# CH32F203RBT6-R1.net
KiCad netlist of a schematic drawn in Altium Designer
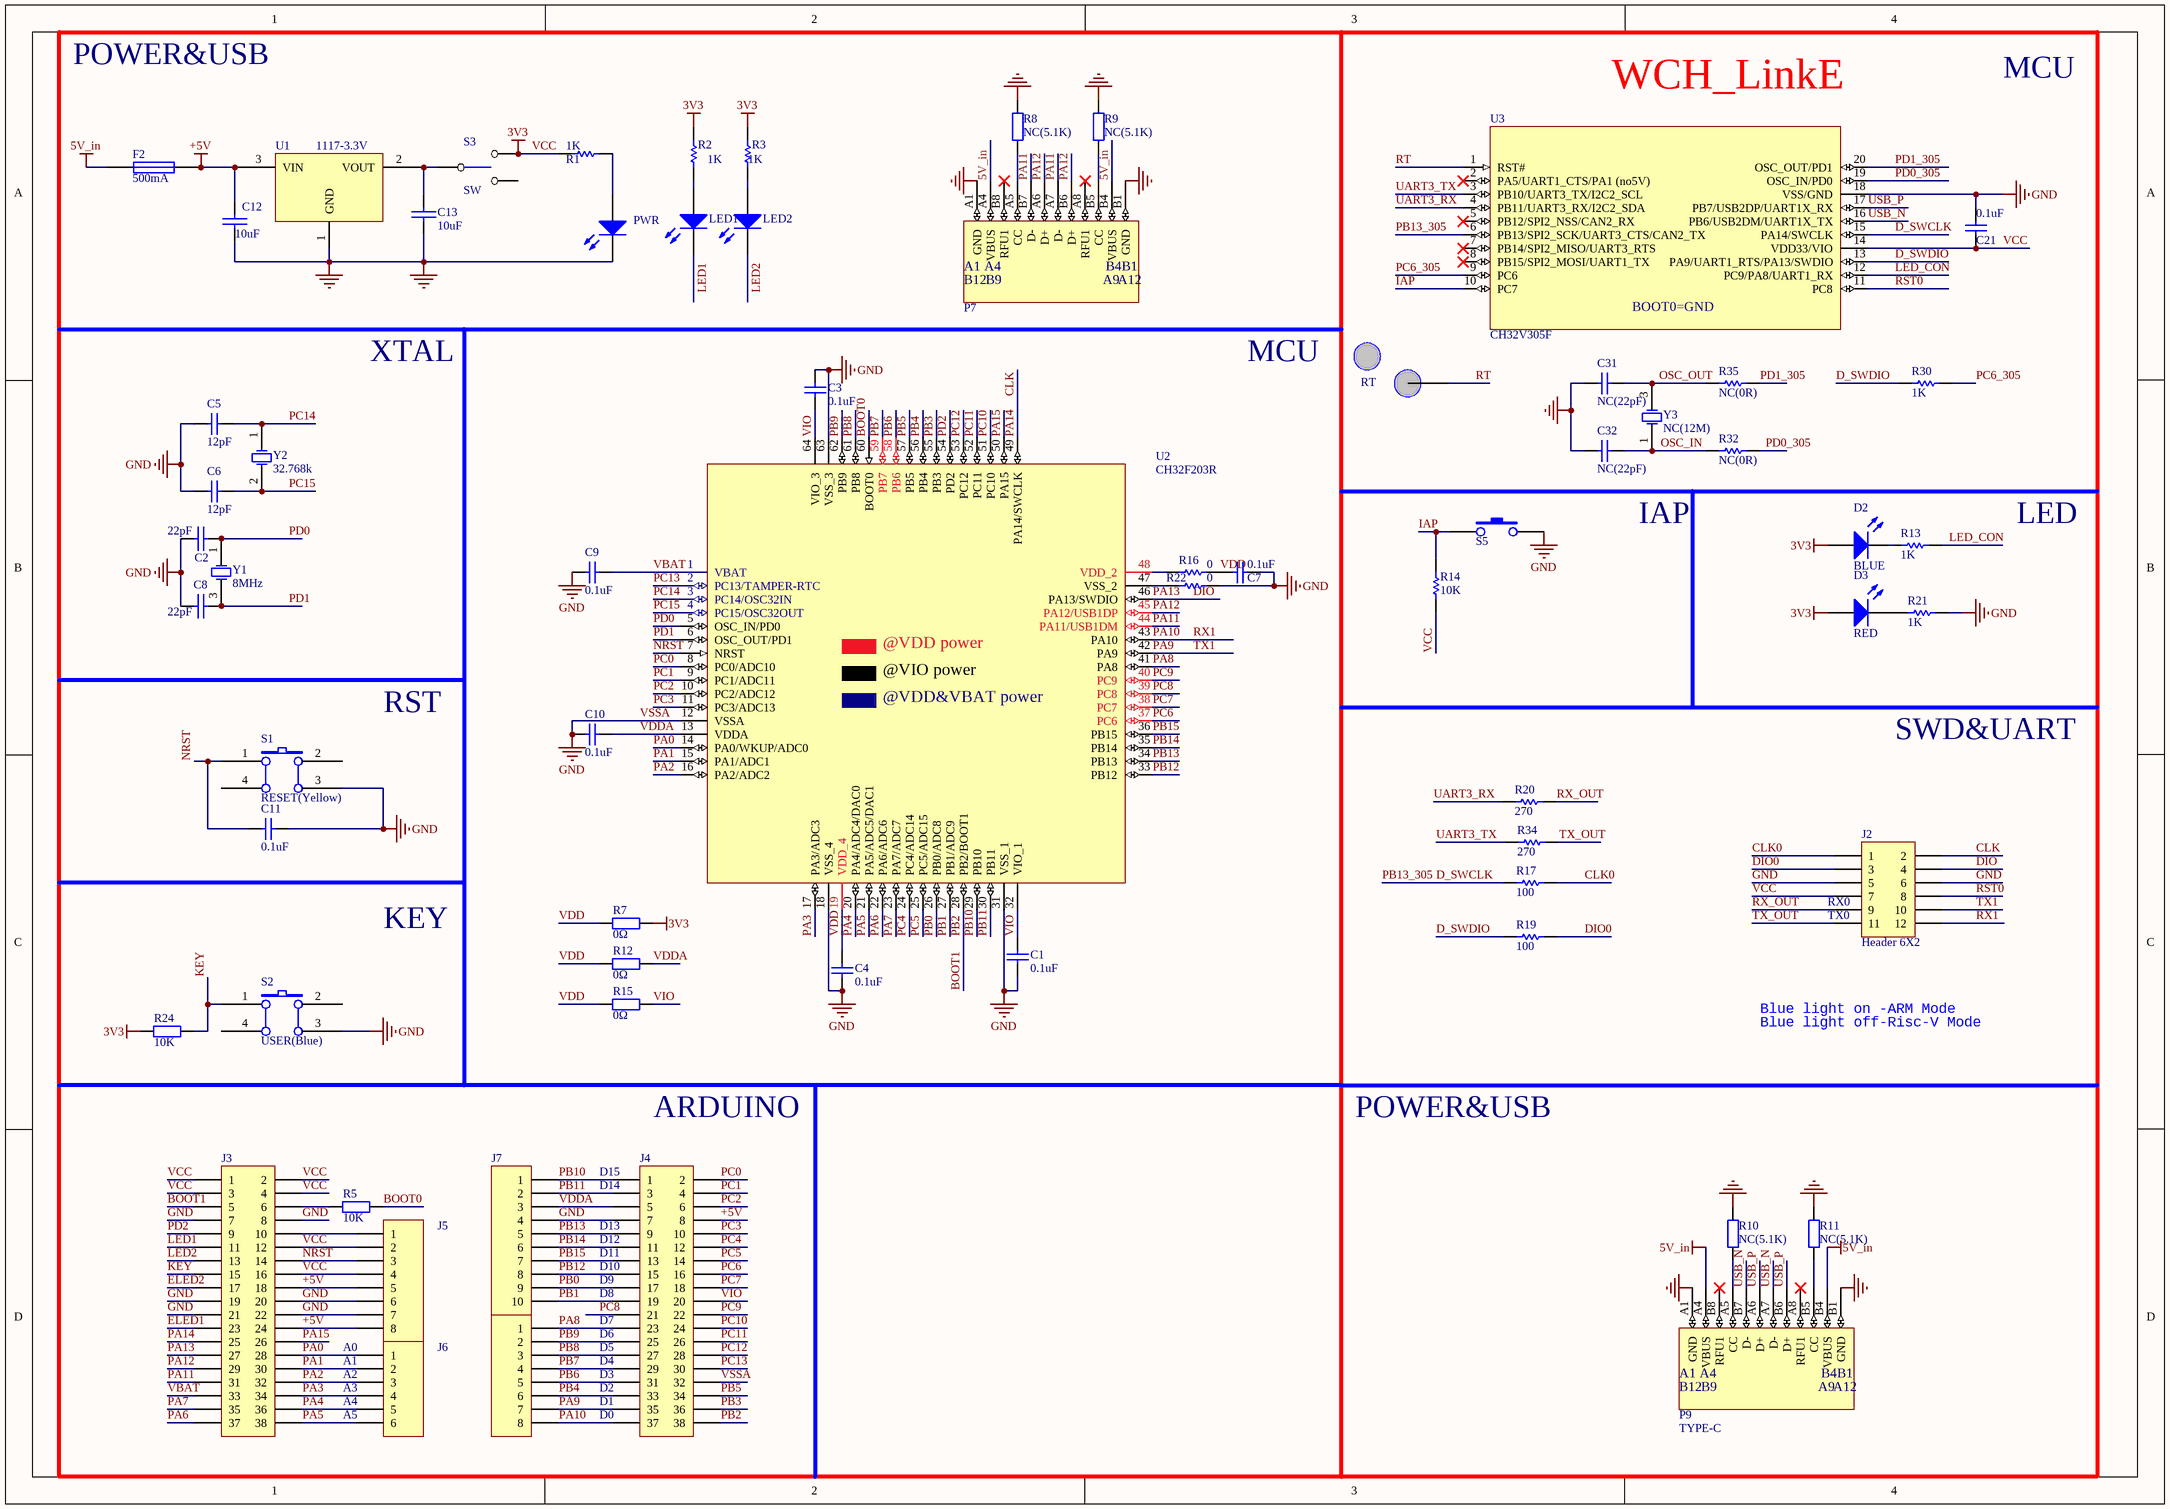
[diagram p0: CH32F203RBT6-R1.SchDoc]

(export (version "E")
  (design (tool "Eeschema 10.0.6"))
  (components
    (comp (ref "C1")
      (value "0.1uF")
      (footprint "0603_C")
      (description "Capacitor")
      (libsource (lib "Miscellaneous Devices") (part "Cap"))
    )
    (comp (ref "C2")
      (value "22pF")
      (footprint "0603_C")
      (description "Capacitor")
      (libsource (lib "*") (part "CAP"))
    )
    (comp (ref "C3")
      (value "0.1uF")
      (footprint "0603_C")
      (description "Capacitor")
      (libsource (lib "Miscellaneous Devices") (part "Cap"))
    )
    (comp (ref "C4")
      (value "0.1uF")
      (footprint "0603_C")
      (description "Capacitor")
      (libsource (lib "Miscellaneous Devices") (part "Cap"))
    )
    (comp (ref "C5")
      (value "12pF")
      (footprint "0603_C")
      (description "Capacitor")
      (libsource (lib "Miscellaneous Devices") (part "Cap"))
    )
    (comp (ref "C6")
      (value "12pF")
      (footprint "0603_C")
      (description "Capacitor")
      (libsource (lib "Miscellaneous Devices") (part "Cap"))
    )
    (comp (ref "C7")
      (value "0.1uF")
      (footprint "0603_C")
      (description "Capacitor")
      (libsource (lib "Miscellaneous Devices") (part "Cap"))
    )
    (comp (ref "C8")
      (value "22pF")
      (footprint "0603_C")
      (description "Capacitor")
      (libsource (lib "*") (part "CAP"))
    )
    (comp (ref "C9")
      (value "0.1uF")
      (footprint "0603_C")
      (description "Capacitor")
      (libsource (lib "Miscellaneous Devices") (part "Cap"))
    )
    (comp (ref "C10")
      (value "0.1uF")
      (footprint "0603_C")
      (description "Capacitor")
      (libsource (lib "Miscellaneous Devices") (part "Cap"))
    )
    (comp (ref "C11")
      (value "0.1uF")
      (footprint "0603_C")
      (description "Capacitor")
      (libsource (lib "Miscellaneous Devices") (part "Cap"))
    )
    (comp (ref "C12")
      (value "10uF")
      (footprint "3216_C")
      (description "Capacitor")
      (libsource (lib "*") (part "CAP"))
    )
    (comp (ref "C13")
      (value "10uF")
      (footprint "3216_C")
      (description "Capacitor")
      (libsource (lib "*") (part "CAP"))
    )
    (comp (ref "C21")
      (value "0.1uF")
      (footprint "0603_C")
      (description "Capacitor")
      (libsource (lib "Miscellaneous Devices") (part "Cap"))
    )
    (comp (ref "C31")
      (value "NC(22pF)")
      (footprint "0603_C")
      (description "Capacitor")
      (fields (field (name "PUBLISHER") "Altium Limited"))
      (libsource (lib "*") (part "Cap"))
    )
    (comp (ref "C32")
      (value "NC(22pF)")
      (footprint "0603_C")
      (description "Capacitor")
      (fields (field (name "PUBLISHER") "Altium Limited"))
      (libsource (lib "*") (part "Cap"))
    )
    (comp (ref "D2")
      (value "BLUE")
      (footprint "0603+")
      (description "Typical RED, GREEN, YELLOW, AMBER GaAs LED")
      (fields (field (name "PUBLISHER") "Altium Limited"))
      (libsource (lib "MYLIB") (part "D0603"))
    )
    (comp (ref "D3")
      (value "RED")
      (footprint "0603+")
      (description "Typical RED, GREEN, YELLOW, AMBER GaAs LED")
      (fields (field (name "PUBLISHER") "Altium Limited"))
      (libsource (lib "MYLIB") (part "D0603"))
    )
    (comp (ref "F2")
      (value "500mA")
      (footprint "0805")
      (description "Fuse")
      (libsource (lib "*") (part "FUSE1"))
    )
    (comp (ref "J2")
      (value "Header 6X2")
      (footprint "IDC12-2.54mm")
      (description "Header, 6-Pin, Dual row")
      (fields (field (name "PUBLISHER") "Altium Limited"))
      (libsource (lib "Miscellaneous Connectors") (part "Header 6X2"))
    )
    (comp (ref "J3")
      (value "Header 19X2")
      (footprint "IDC38-2.54mm")
      (description "Header, 19-Pin, Dual row")
      (fields (field (name "PUBLISHER") "Altium Limited"))
      (libsource (lib "Miscellaneous Connectors") (part "Header 19X2"))
    )
    (comp (ref "J4")
      (value "Header 19X2")
      (footprint "IDC38-2.54mm")
      (description "Header, 19-Pin, Dual row")
      (fields (field (name "PUBLISHER") "Altium Limited"))
      (libsource (lib "Miscellaneous Connectors") (part "Header 19X2"))
    )
    (comp (ref "J5")
      (value "Header 8")
      (footprint "SIP8-2.54mm")
      (description "Header, 8-Pin")
      (fields (field (name "PUBLISHER") "Altium Limited"))
      (libsource (lib "") (part "Header 8_1"))
    )
    (comp (ref "J6")
      (value "Header 6")
      (footprint "SIP6-2.54MM")
      (description "Header, 6-Pin")
      (fields (field (name "PUBLISHER") "Altium Limited"))
      (libsource (lib "Miscellaneous Connectors") (part "Header 6"))
    )
    (comp (ref "J7")
      (value "Header 10")
      (footprint "SIP10-2.54mm")
      (description "Header, 10-Pin")
      (fields (field (name "PUBLISHER") "Altium Limited"))
      (libsource (lib "Miscellaneous Connectors") (part "Header 10"))
    )
    (comp (ref "J8")
      (value "Header 8")
      (footprint "SIP8-2.54mm")
      (description "Header, 8-Pin")
      (fields (field (name "PUBLISHER") "Altium Limited"))
      (libsource (lib "Miscellaneous Connectors") (part "Header 8"))
    )
    (comp (ref "LED1")
      (value "LED1   blue")
      (footprint "0603+")
      (description "Typical INFRARED GaAs LED")
      (fields (field (name "PUBLISHER") "Altium Limited"))
      (libsource (lib "Miscellaneous Devices") (part "LED0"))
    )
    (comp (ref "LED2")
      (value "LED2  blue")
      (footprint "0603+")
      (description "Typical INFRARED GaAs LED")
      (fields (field (name "PUBLISHER") "Altium Limited"))
      (libsource (lib "Miscellaneous Devices") (part "LED0"))
    )
    (comp (ref "P7")
      (value "TYPE-C")
      (footprint "TYPE-C-Receptacle-2.0")
      (libsource (lib "*") (part "TYPE-C1"))
    )
    (comp (ref "P9")
      (value "TYPE-C")
      (footprint "TYPE-C-Receptacle-2.0")
      (libsource (lib "*") (part "TYPE-C1"))
    )
    (comp (ref "PWR")
      (value "POWER  red")
      (footprint "0603+")
      (description "Typical INFRARED GaAs LED")
      (fields (field (name "PUBLISHER") "Altium Limited"))
      (libsource (lib "Miscellaneous Devices") (part "LED0"))
    )
    (comp (ref "R1")
      (value "1K")
      (footprint "0603")
      (description "Semiconductor Resistor")
      (libsource (lib "Miscellaneous Devices") (part "Res Semi"))
    )
    (comp (ref "R2")
      (value "1K")
      (footprint "0603")
      (description "Semiconductor Resistor")
      (libsource (lib "Miscellaneous Devices") (part "Res Semi"))
    )
    (comp (ref "R3")
      (value "1K")
      (footprint "0603")
      (description "Semiconductor Resistor")
      (libsource (lib "Miscellaneous Devices") (part "Res Semi"))
    )
    (comp (ref "R5")
      (value "10K")
      (footprint "0603")
      (description "Resistor")
      (libsource (lib "") (part "Res2_2"))
    )
    (comp (ref "R7")
      (value "0Ω")
      (footprint "0603")
      (description "Resistor")
      (libsource (lib "Miscellaneous Devices") (part "Res2"))
    )
    (comp (ref "R8")
      (value "NC(5.1K)")
      (footprint "0603")
      (description "Resistor")
      (libsource (lib "") (part "Res2_1"))
    )
    (comp (ref "R9")
      (value "NC(5.1K)")
      (footprint "0603")
      (description "Resistor")
      (libsource (lib "") (part "Res2_1"))
    )
    (comp (ref "R10")
      (value "NC(5.1K)")
      (footprint "0603")
      (description "Resistor")
      (libsource (lib "") (part "Res2_3"))
    )
    (comp (ref "R11")
      (value "NC(5.1K)")
      (footprint "0603")
      (description "Resistor")
      (libsource (lib "") (part "Res2_3"))
    )
    (comp (ref "R12")
      (value "0Ω")
      (footprint "0603")
      (description "Resistor")
      (libsource (lib "Miscellaneous Devices") (part "Res2"))
    )
    (comp (ref "R13")
      (value "1K")
      (footprint "0603")
      (description "Resistor")
      (fields (field (name "PUBLISHER") "Altium Limited"))
      (libsource (lib "MYLIB") (part "0603-1"))
    )
    (comp (ref "R14")
      (value "10K")
      (footprint "0603")
      (description "Resistor")
      (fields (field (name "PUBLISHER") "Altium Limited"))
      (libsource (lib "MYLIB") (part "0603-1"))
    )
    (comp (ref "R15")
      (value "0Ω")
      (footprint "0603")
      (description "Resistor")
      (libsource (lib "Miscellaneous Devices") (part "Res2"))
    )
    (comp (ref "R16")
      (value "0")
      (footprint "0603")
      (description "Resistor")
      (fields (field (name "PUBLISHER") "Altium Limited"))
      (libsource (lib "MYLIB") (part "0603-1"))
    )
    (comp (ref "R17")
      (value "100")
      (footprint "0603")
      (description "Resistor")
      (fields (field (name "PUBLISHER") "Altium Limited"))
      (libsource (lib "MYLIB") (part "0603-1"))
    )
    (comp (ref "R19")
      (value "100")
      (footprint "0603")
      (description "Resistor")
      (fields (field (name "PUBLISHER") "Altium Limited"))
      (libsource (lib "MYLIB") (part "0603-1"))
    )
    (comp (ref "R20")
      (value "270")
      (footprint "0603")
      (description "Resistor")
      (fields (field (name "PUBLISHER") "Altium Limited"))
      (libsource (lib "MYLIB") (part "0603-1"))
    )
    (comp (ref "R21")
      (value "1K")
      (footprint "0603")
      (description "Resistor")
      (fields (field (name "PUBLISHER") "Altium Limited"))
      (libsource (lib "MYLIB") (part "0603-1"))
    )
    (comp (ref "R22")
      (value "0")
      (footprint "0603")
      (description "Resistor")
      (fields (field (name "PUBLISHER") "Altium Limited"))
      (libsource (lib "MYLIB") (part "0603-1"))
    )
    (comp (ref "R24")
      (value "10K")
      (footprint "0603")
      (description "Resistor")
      (libsource (lib "Miscellaneous Devices") (part "Res2"))
    )
    (comp (ref "R30")
      (value "1K")
      (footprint "0603")
      (description "Resistor")
      (fields (field (name "PUBLISHER") "Altium Limited"))
      (libsource (lib "MYLIB") (part "0603-1"))
    )
    (comp (ref "R32")
      (value "NC(0R)")
      (footprint "0603")
      (description "Resistor")
      (fields (field (name "PUBLISHER") "Altium Limited"))
      (libsource (lib "MYLIB") (part "0603-1"))
    )
    (comp (ref "R34")
      (value "270")
      (footprint "0603")
      (description "Resistor")
      (fields (field (name "PUBLISHER") "Altium Limited"))
      (libsource (lib "MYLIB") (part "0603-1"))
    )
    (comp (ref "R35")
      (value "NC(0R)")
      (footprint "0603")
      (description "Resistor")
      (fields (field (name "PUBLISHER") "Altium Limited"))
      (libsource (lib "MYLIB") (part "0603-1"))
    )
    (comp (ref "RT")
      (value "Testpoint")
      (footprint "TESTPOINT1")
      (description "测试点")
      (libsource (lib "wch_sch_others") (part "Testpoint"))
    )
    (comp (ref "S1")
      (value "RESET(Yellow)")
      (footprint "KEYX")
      (description "SE PUSHBUTTON")
      (libsource (lib "Documents") (part "SW PUSHBUTTON"))
    )
    (comp (ref "S2")
      (value "USER(Blue)")
      (footprint "KEYX")
      (description "SE PUSHBUTTON")
      (libsource (lib "Documents") (part "SW PUSHBUTTON"))
    )
    (comp (ref "S3") (value "SW") (footprint "SW1") (libsource (lib "MYSCH") (part "SW")))
    (comp (ref "S5") (value "KEY") (footprint "贴片按键") (libsource (lib "*") (part "KEY")))
    (comp (ref "U1")
      (value "1117-3.3V")
      (footprint "SOT-223")
      (libsource (lib "wch_sch_others") (part "1117-3.3V"))
    )
    (comp (ref "U2")
      (value "CH32F203R")
      (footprint "LQFP64M_10x10")
      (description "ARM M3 HD-MCU, 144MHz, 8*UART, 10*Timer, 4*OPA")
      (libsource (lib "CHXXX") (part "CH32F203R"))
    )
    (comp (ref "U3")
      (value "CH32V305F")
      (footprint "TSSOP20")
      (description "RISC-V FPU HD-MCU, 144MHz, USB_480M, CAN, UART*2, SPI")
      (libsource (lib "CHXXX") (part "CH32V305F"))
    )
    (comp (ref "Y1")
      (value "8MHz")
      (footprint "XT3225")
      (description "Crystal Oscillator")
      (fields (field (name "PUBLISHER") "Altium Limited"))
      (libsource (lib "*") (part "XTAL"))
    )
    (comp (ref "Y2")
      (value "32.768k")
      (footprint "FC-135")
      (description "Crystal Oscillator")
      (fields (field (name "PUBLISHER") "Altium Limited"))
      (libsource (lib "Miscellaneous Devices") (part "XTAL"))
    )
    (comp (ref "Y3")
      (value "NC(12M)")
      (footprint "XT3225")
      (description "Crystal Oscillator")
      (libsource (lib "*") (part "XTAL"))
    )
  )
  (nets
    (net (code "1") (name "+5V") (class "Default")
      (node (ref "C12") (pin "1") (pinfunction "1_1") (pintype "passive"))
      (node (ref "F2") (pin "2") (pinfunction "2_2") (pintype "passive"))
      (node (ref "J3") (pin "18") (pinfunction "18_18") (pintype "passive"))
      (node (ref "J3") (pin "24") (pinfunction "24_24") (pintype "passive"))
      (node (ref "J4") (pin "8") (pinfunction "8_8") (pintype "passive"))
      (node (ref "J5") (pin "5") (pinfunction "5_5") (pintype "passive"))
      (node (ref "J5") (pin "8") (pinfunction "8_8") (pintype "passive"))
      (node (ref "U1") (pin "3") (pinfunction "VIN_3") (pintype "passive"))
    )
    (net (code "2") (name "/BOOT0") (class "Default")
      (node (ref "R5") (pin "2") (pinfunction "2_2") (pintype "passive"))
      (node (ref "U2") (pin "60") (pinfunction "BOOT0_60") (pintype "input"))
    )
    (net (code "3") (name "/BOOT1") (class "Default")
      (node (ref "J3") (pin "5") (pinfunction "5_5") (pintype "passive"))
      (node (ref "J4") (pin "38") (pinfunction "38_38") (pintype "passive"))
      (node (ref "U2") (pin "28") (pinfunction "PB2/BOOT1_28") (pintype "bidirectional"))
    )
    (net (code "4") (name "/CLK") (class "Default")
      (node (ref "J2") (pin "2") (pinfunction "2_2") (pintype "passive"))
      (node (ref "J3") (pin "25") (pinfunction "25_25") (pintype "passive"))
      (node (ref "U2") (pin "49") (pinfunction "PA14/SWCLK_49") (pintype "bidirectional"))
    )
    (net (code "5") (name "/CLK0") (class "Default")
      (node (ref "J2") (pin "1") (pinfunction "1_1") (pintype "passive"))
      (node (ref "R17") (pin "1") (pinfunction "1_1") (pintype "passive"))
    )
    (net (code "6") (name "/DIO") (class "Default")
      (node (ref "J2") (pin "4") (pinfunction "4_4") (pintype "passive"))
      (node (ref "J3") (pin "27") (pinfunction "27_27") (pintype "passive"))
      (node (ref "U2") (pin "46") (pinfunction "PA13/SWDIO_46") (pintype "bidirectional"))
    )
    (net (code "7") (name "/DIO0") (class "Default")
      (node (ref "J2") (pin "3") (pinfunction "3_3") (pintype "passive"))
      (node (ref "R19") (pin "1") (pinfunction "1_1") (pintype "passive"))
    )
    (net (code "8") (name "/D_SWCLK") (class "Default")
      (node (ref "R17") (pin "2") (pinfunction "2_2") (pintype "passive"))
      (node (ref "U3") (pin "15") (pinfunction "PA14/SWCLK_15") (pintype "bidirectional"))
      (node (ref "U3") (pin "6") (pinfunction "PB13/SPI2_SCK/UART3_CTS/CAN2_TX_6") (pintype "bidirectional"))
    )
    (net (code "9") (name "/D_SWDIO") (class "Default")
      (node (ref "R19") (pin "2") (pinfunction "2_2") (pintype "passive"))
      (node (ref "R30") (pin "1") (pinfunction "1_1") (pintype "passive"))
      (node (ref "U3") (pin "13") (pinfunction "PA9/UART1_RTS/PA13/SWDIO_13") (pintype "bidirectional"))
    )
    (net (code "10") (name "/ELED1") (class "Default")
      (node (ref "J3") (pin "23") (pinfunction "23_23") (pintype "passive"))
    )
    (net (code "11") (name "/ELED2") (class "Default")
      (node (ref "J3") (pin "17") (pinfunction "17_17") (pintype "passive"))
    )
    (net (code "12") (name "/IAP") (class "Default")
      (node (ref "R14") (pin "1") (pinfunction "1_1") (pintype "passive"))
      (node (ref "S5") (pin "1") (pinfunction "1_1") (pintype "passive"))
      (node (ref "U3") (pin "10") (pinfunction "PC7_10") (pintype "bidirectional"))
    )
    (net (code "13") (name "/KEY") (class "Default")
      (node (ref "J3") (pin "15") (pinfunction "15_15") (pintype "passive"))
      (node (ref "R24") (pin "1") (pinfunction "1_1") (pintype "passive"))
      (node (ref "S2") (pin "1") (pinfunction "A0_1") (pintype "passive"))
    )
    (net (code "14") (name "/LED1") (class "Default")
      (node (ref "J3") (pin "11") (pinfunction "11_11") (pintype "passive"))
      (node (ref "LED1") (pin "2") (pinfunction "K_2") (pintype "passive"))
    )
    (net (code "15") (name "/LED2") (class "Default")
      (node (ref "J3") (pin "13") (pinfunction "13_13") (pintype "passive"))
      (node (ref "LED2") (pin "2") (pinfunction "K_2") (pintype "passive"))
    )
    (net (code "16") (name "/LED_CON") (class "Default")
      (node (ref "R13") (pin "1") (pinfunction "1_1") (pintype "passive"))
      (node (ref "U3") (pin "12") (pinfunction "PC9/PA8/UART1_RX_12") (pintype "bidirectional"))
    )
    (net (code "17") (name "/NRST") (class "Default")
      (node (ref "C11") (pin "2") (pinfunction "2_2") (pintype "passive"))
      (node (ref "J3") (pin "14") (pinfunction "14_14") (pintype "passive"))
      (node (ref "J5") (pin "3") (pinfunction "3_3") (pintype "passive"))
      (node (ref "S1") (pin "1") (pinfunction "A0_1") (pintype "passive"))
      (node (ref "U2") (pin "7") (pinfunction "NRST_7") (pintype "input"))
    )
    (net (code "18") (name "/OSC_IN") (class "Default")
      (node (ref "C32") (pin "2") (pinfunction "2_2") (pintype "passive"))
      (node (ref "R32") (pin "2") (pinfunction "2_2") (pintype "passive"))
      (node (ref "Y3") (pin "1") (pinfunction "OSC1_1") (pintype "passive"))
    )
    (net (code "19") (name "/OSC_OUT") (class "Default")
      (node (ref "C31") (pin "2") (pinfunction "2_2") (pintype "passive"))
      (node (ref "R35") (pin "2") (pinfunction "2_2") (pintype "passive"))
      (node (ref "Y3") (pin "3") (pinfunction "OSC2_3") (pintype "passive"))
    )
    (net (code "20") (name "/PA0") (class "Default")
      (node (ref "J3") (pin "28") (pinfunction "28_28") (pintype "passive"))
      (node (ref "J6") (pin "1") (pinfunction "1_1") (pintype "passive"))
      (node (ref "U2") (pin "14") (pinfunction "PA0/WKUP/ADC0_14") (pintype "bidirectional"))
    )
    (net (code "21") (name "/PA1") (class "Default")
      (node (ref "J3") (pin "30") (pinfunction "30_30") (pintype "passive"))
      (node (ref "J6") (pin "2") (pinfunction "2_2") (pintype "passive"))
      (node (ref "U2") (pin "15") (pinfunction "PA1/ADC1_15") (pintype "bidirectional"))
    )
    (net (code "22") (name "/PA2") (class "Default")
      (node (ref "J3") (pin "32") (pinfunction "32_32") (pintype "passive"))
      (node (ref "J6") (pin "3") (pinfunction "3_3") (pintype "passive"))
      (node (ref "U2") (pin "16") (pinfunction "PA2/ADC2_16") (pintype "bidirectional"))
    )
    (net (code "23") (name "/PA3") (class "Default")
      (node (ref "J3") (pin "34") (pinfunction "34_34") (pintype "passive"))
      (node (ref "J6") (pin "4") (pinfunction "4_4") (pintype "passive"))
      (node (ref "U2") (pin "17") (pinfunction "PA3/ADC3_17") (pintype "bidirectional"))
    )
    (net (code "24") (name "/PA4") (class "Default")
      (node (ref "J3") (pin "36") (pinfunction "36_36") (pintype "passive"))
      (node (ref "J6") (pin "5") (pinfunction "5_5") (pintype "passive"))
      (node (ref "U2") (pin "20") (pinfunction "PA4/ADC4/DAC0_20") (pintype "bidirectional"))
    )
    (net (code "25") (name "/PA5") (class "Default")
      (node (ref "J3") (pin "38") (pinfunction "38_38") (pintype "passive"))
      (node (ref "J6") (pin "6") (pinfunction "6_6") (pintype "passive"))
      (node (ref "U2") (pin "21") (pinfunction "PA5/ADC5/DAC1_21") (pintype "bidirectional"))
    )
    (net (code "26") (name "/PA6") (class "Default")
      (node (ref "J3") (pin "37") (pinfunction "37_37") (pintype "passive"))
      (node (ref "U2") (pin "22") (pinfunction "PA6/ADC6_22") (pintype "bidirectional"))
    )
    (net (code "27") (name "/PA7") (class "Default")
      (node (ref "J3") (pin "35") (pinfunction "35_35") (pintype "passive"))
      (node (ref "U2") (pin "23") (pinfunction "PA7/ADC7_23") (pintype "bidirectional"))
    )
    (net (code "28") (name "/PA8") (class "Default")
      (node (ref "J4") (pin "23") (pinfunction "23_23") (pintype "passive"))
      (node (ref "J8") (pin "1") (pinfunction "1_1") (pintype "passive"))
      (node (ref "U2") (pin "41") (pinfunction "PA8_41") (pintype "bidirectional"))
    )
    (net (code "29") (name "/PA9") (class "Default")
      (node (ref "J2") (pin "10") (pinfunction "10_10") (pintype "passive"))
      (node (ref "J4") (pin "35") (pinfunction "35_35") (pintype "passive"))
      (node (ref "J8") (pin "7") (pinfunction "7_7") (pintype "passive"))
      (node (ref "U2") (pin "42") (pinfunction "PA9_42") (pintype "bidirectional"))
    )
    (net (code "30") (name "/PA10") (class "Default")
      (node (ref "J2") (pin "12") (pinfunction "12_12") (pintype "passive"))
      (node (ref "J4") (pin "37") (pinfunction "37_37") (pintype "passive"))
      (node (ref "J8") (pin "8") (pinfunction "8_8") (pintype "passive"))
      (node (ref "U2") (pin "43") (pinfunction "PA10_43") (pintype "bidirectional"))
    )
    (net (code "31") (name "/PA11") (class "Default")
      (node (ref "J3") (pin "31") (pinfunction "31_31") (pintype "passive"))
      (node (ref "P7") (pin "A7") (pinfunction "D-_A7") (pintype "bidirectional"))
      (node (ref "P7") (pin "B7") (pinfunction "D-_B7") (pintype "bidirectional"))
      (node (ref "U2") (pin "44") (pinfunction "PA11/USB1DM_44") (pintype "bidirectional"))
    )
    (net (code "32") (name "/PA12") (class "Default")
      (node (ref "J3") (pin "29") (pinfunction "29_29") (pintype "passive"))
      (node (ref "P7") (pin "A6") (pinfunction "D+_A6") (pintype "bidirectional"))
      (node (ref "P7") (pin "B6") (pinfunction "D+_B6") (pintype "bidirectional"))
      (node (ref "U2") (pin "45") (pinfunction "PA12/USB1DP_45") (pintype "bidirectional"))
    )
    (net (code "33") (name "/PA15") (class "Default")
      (node (ref "J3") (pin "26") (pinfunction "26_26") (pintype "passive"))
      (node (ref "U2") (pin "50") (pinfunction "PA15_50") (pintype "bidirectional"))
    )
    (net (code "34") (name "/PB0") (class "Default")
      (node (ref "J4") (pin "17") (pinfunction "17_17") (pintype "passive"))
      (node (ref "J7") (pin "9") (pinfunction "9_9") (pintype "passive"))
      (node (ref "U2") (pin "26") (pinfunction "PB0/ADC8_26") (pintype "bidirectional"))
    )
    (net (code "35") (name "/PB1") (class "Default")
      (node (ref "J4") (pin "19") (pinfunction "19_19") (pintype "passive"))
      (node (ref "J7") (pin "10") (pinfunction "10_10") (pintype "passive"))
      (node (ref "U2") (pin "27") (pinfunction "PB1/ADC9_27") (pintype "bidirectional"))
    )
    (net (code "36") (name "/PB3") (class "Default")
      (node (ref "J4") (pin "36") (pinfunction "36_36") (pintype "passive"))
      (node (ref "U2") (pin "55") (pinfunction "PB3_55") (pintype "bidirectional"))
    )
    (net (code "37") (name "/PB4") (class "Default")
      (node (ref "J4") (pin "33") (pinfunction "33_33") (pintype "passive"))
      (node (ref "J8") (pin "6") (pinfunction "6_6") (pintype "passive"))
      (node (ref "U2") (pin "56") (pinfunction "PB4_56") (pintype "bidirectional"))
    )
    (net (code "38") (name "/PB5") (class "Default")
      (node (ref "J4") (pin "34") (pinfunction "34_34") (pintype "passive"))
      (node (ref "U2") (pin "57") (pinfunction "PB5_57") (pintype "bidirectional"))
    )
    (net (code "39") (name "/PB6") (class "Default")
      (node (ref "J4") (pin "31") (pinfunction "31_31") (pintype "passive"))
      (node (ref "J8") (pin "5") (pinfunction "5_5") (pintype "passive"))
      (node (ref "U2") (pin "58") (pinfunction "PB6_58") (pintype "bidirectional"))
    )
    (net (code "40") (name "/PB7") (class "Default")
      (node (ref "J4") (pin "29") (pinfunction "29_29") (pintype "passive"))
      (node (ref "J8") (pin "4") (pinfunction "4_4") (pintype "passive"))
      (node (ref "U2") (pin "59") (pinfunction "PB7_59") (pintype "bidirectional"))
    )
    (net (code "41") (name "/PB8") (class "Default")
      (node (ref "J4") (pin "27") (pinfunction "27_27") (pintype "passive"))
      (node (ref "J8") (pin "3") (pinfunction "3_3") (pintype "passive"))
      (node (ref "U2") (pin "61") (pinfunction "PB8_61") (pintype "bidirectional"))
    )
    (net (code "42") (name "/PB9") (class "Default")
      (node (ref "J4") (pin "25") (pinfunction "25_25") (pintype "passive"))
      (node (ref "J8") (pin "2") (pinfunction "2_2") (pintype "passive"))
      (node (ref "U2") (pin "62") (pinfunction "PB9_62") (pintype "bidirectional"))
    )
    (net (code "43") (name "/PB10") (class "Default")
      (node (ref "J4") (pin "1") (pinfunction "1_1") (pintype "passive"))
      (node (ref "J7") (pin "1") (pinfunction "1_1") (pintype "passive"))
      (node (ref "U2") (pin "29") (pinfunction "PB10_29") (pintype "bidirectional"))
    )
    (net (code "44") (name "/PB11") (class "Default")
      (node (ref "J4") (pin "3") (pinfunction "3_3") (pintype "passive"))
      (node (ref "J7") (pin "2") (pinfunction "2_2") (pintype "passive"))
      (node (ref "U2") (pin "30") (pinfunction "PB11_30") (pintype "bidirectional"))
    )
    (net (code "45") (name "/PB12") (class "Default")
      (node (ref "J4") (pin "15") (pinfunction "15_15") (pintype "passive"))
      (node (ref "J7") (pin "8") (pinfunction "8_8") (pintype "passive"))
      (node (ref "U2") (pin "33") (pinfunction "PB12_33") (pintype "bidirectional"))
    )
    (net (code "46") (name "/PB13") (class "Default")
      (node (ref "J4") (pin "9") (pinfunction "9_9") (pintype "passive"))
      (node (ref "J7") (pin "5") (pinfunction "5_5") (pintype "passive"))
      (node (ref "U2") (pin "34") (pinfunction "PB13_34") (pintype "bidirectional"))
    )
    (net (code "47") (name "/PB14") (class "Default")
      (node (ref "J4") (pin "11") (pinfunction "11_11") (pintype "passive"))
      (node (ref "J7") (pin "6") (pinfunction "6_6") (pintype "passive"))
      (node (ref "U2") (pin "35") (pinfunction "PB14_35") (pintype "bidirectional"))
    )
    (net (code "48") (name "/PB15") (class "Default")
      (node (ref "J4") (pin "13") (pinfunction "13_13") (pintype "passive"))
      (node (ref "J7") (pin "7") (pinfunction "7_7") (pintype "passive"))
      (node (ref "U2") (pin "36") (pinfunction "PB15_36") (pintype "bidirectional"))
    )
    (net (code "49") (name "/PC0") (class "Default")
      (node (ref "J4") (pin "2") (pinfunction "2_2") (pintype "passive"))
      (node (ref "U2") (pin "8") (pinfunction "PC0/ADC10_8") (pintype "bidirectional"))
    )
    (net (code "50") (name "/PC1") (class "Default")
      (node (ref "J4") (pin "4") (pinfunction "4_4") (pintype "passive"))
      (node (ref "U2") (pin "9") (pinfunction "PC1/ADC11_9") (pintype "bidirectional"))
    )
    (net (code "51") (name "/PC2") (class "Default")
      (node (ref "J4") (pin "6") (pinfunction "6_6") (pintype "passive"))
      (node (ref "U2") (pin "10") (pinfunction "PC2/ADC12_10") (pintype "bidirectional"))
    )
    (net (code "52") (name "/PC3") (class "Default")
      (node (ref "J4") (pin "10") (pinfunction "10_10") (pintype "passive"))
      (node (ref "U2") (pin "11") (pinfunction "PC3/ADC13_11") (pintype "bidirectional"))
    )
    (net (code "53") (name "/PC4") (class "Default")
      (node (ref "J4") (pin "12") (pinfunction "12_12") (pintype "passive"))
      (node (ref "U2") (pin "24") (pinfunction "PC4/ADC14_24") (pintype "bidirectional"))
    )
    (net (code "54") (name "/PC5") (class "Default")
      (node (ref "J4") (pin "14") (pinfunction "14_14") (pintype "passive"))
      (node (ref "U2") (pin "25") (pinfunction "PC5/ADC15_25") (pintype "bidirectional"))
    )
    (net (code "55") (name "/PC6") (class "Default")
      (node (ref "J4") (pin "16") (pinfunction "16_16") (pintype "passive"))
      (node (ref "U2") (pin "37") (pinfunction "PC6_37") (pintype "bidirectional"))
    )
    (net (code "56") (name "/PC6_305") (class "Default")
      (node (ref "R30") (pin "2") (pinfunction "2_2") (pintype "passive"))
      (node (ref "U3") (pin "9") (pinfunction "PC6_9") (pintype "bidirectional"))
    )
    (net (code "57") (name "/PC7") (class "Default")
      (node (ref "J4") (pin "18") (pinfunction "18_18") (pintype "passive"))
      (node (ref "U2") (pin "38") (pinfunction "PC7_38") (pintype "bidirectional"))
    )
    (net (code "58") (name "/PC8") (class "Default")
      (node (ref "J4") (pin "21") (pinfunction "21_21") (pintype "passive"))
      (node (ref "U2") (pin "39") (pinfunction "PC8_39") (pintype "bidirectional"))
    )
    (net (code "59") (name "/PC9") (class "Default")
      (node (ref "J4") (pin "22") (pinfunction "22_22") (pintype "passive"))
      (node (ref "U2") (pin "40") (pinfunction "PC9_40") (pintype "bidirectional"))
    )
    (net (code "60") (name "/PC10") (class "Default")
      (node (ref "J4") (pin "24") (pinfunction "24_24") (pintype "passive"))
      (node (ref "U2") (pin "51") (pinfunction "PC10_51") (pintype "bidirectional"))
    )
    (net (code "61") (name "/PC11") (class "Default")
      (node (ref "J4") (pin "26") (pinfunction "26_26") (pintype "passive"))
      (node (ref "U2") (pin "52") (pinfunction "PC11_52") (pintype "bidirectional"))
    )
    (net (code "62") (name "/PC12") (class "Default")
      (node (ref "J4") (pin "28") (pinfunction "28_28") (pintype "passive"))
      (node (ref "U2") (pin "53") (pinfunction "PC12_53") (pintype "bidirectional"))
    )
    (net (code "63") (name "/PC13") (class "Default")
      (node (ref "J4") (pin "30") (pinfunction "30_30") (pintype "passive"))
      (node (ref "U2") (pin "2") (pinfunction "PC13/TAMPER-RTC_2") (pintype "bidirectional"))
    )
    (net (code "64") (name "/PC14") (class "Default")
      (node (ref "C5") (pin "1") (pinfunction "1_1") (pintype "passive"))
      (node (ref "U2") (pin "3") (pinfunction "PC14/OSC32IN_3") (pintype "bidirectional"))
      (node (ref "Y2") (pin "1") (pinfunction "OSC1_1") (pintype "passive"))
    )
    (net (code "65") (name "/PC15") (class "Default")
      (node (ref "C6") (pin "1") (pinfunction "1_1") (pintype "passive"))
      (node (ref "U2") (pin "4") (pinfunction "PC15/OSC32OUT_4") (pintype "bidirectional"))
      (node (ref "Y2") (pin "2") (pinfunction "OSC2_2") (pintype "passive"))
    )
    (net (code "66") (name "/PD0") (class "Default")
      (node (ref "C2") (pin "2") (pinfunction "2_2") (pintype "passive"))
      (node (ref "U2") (pin "5") (pinfunction "OSC_IN/PD0_5") (pintype "bidirectional"))
      (node (ref "Y1") (pin "1") (pinfunction "OSC1_1") (pintype "passive"))
    )
    (net (code "67") (name "/PD0_305") (class "Default")
      (node (ref "R32") (pin "1") (pinfunction "1_1") (pintype "passive"))
      (node (ref "U3") (pin "19") (pinfunction "OSC_IN/PD0_19") (pintype "bidirectional"))
    )
    (net (code "68") (name "/PD1") (class "Default")
      (node (ref "C8") (pin "2") (pinfunction "2_2") (pintype "passive"))
      (node (ref "U2") (pin "6") (pinfunction "OSC_OUT/PD1_6") (pintype "bidirectional"))
      (node (ref "Y1") (pin "3") (pinfunction "OSC2_3") (pintype "passive"))
    )
    (net (code "69") (name "/PD1_305") (class "Default")
      (node (ref "R35") (pin "1") (pinfunction "1_1") (pintype "passive"))
      (node (ref "U3") (pin "20") (pinfunction "OSC_OUT/PD1_20") (pintype "bidirectional"))
    )
    (net (code "70") (name "/PD2") (class "Default")
      (node (ref "J3") (pin "9") (pinfunction "9_9") (pintype "passive"))
      (node (ref "U2") (pin "54") (pinfunction "PD2_54") (pintype "bidirectional"))
    )
    (net (code "71") (name "/RST0") (class "Default")
      (node (ref "J2") (pin "8") (pinfunction "8_8") (pintype "passive"))
      (node (ref "U3") (pin "11") (pinfunction "PC8_11") (pintype "bidirectional"))
    )
    (net (code "72") (name "/RT") (class "Default")
      (node (ref "RT") (pin "1") (pinfunction "point_1") (pintype "passive"))
      (node (ref "U3") (pin "1") (pinfunction "RST#_1") (pintype "input"))
    )
    (net (code "73") (name "/RX_OUT") (class "Default")
      (node (ref "J2") (pin "9") (pinfunction "9_9") (pintype "passive"))
      (node (ref "R20") (pin "1") (pinfunction "1_1") (pintype "passive"))
    )
    (net (code "74") (name "/TX_OUT") (class "Default")
      (node (ref "J2") (pin "11") (pinfunction "11_11") (pintype "passive"))
      (node (ref "R34") (pin "1") (pinfunction "1_1") (pintype "passive"))
    )
    (net (code "75") (name "/UART3_RX") (class "Default")
      (node (ref "R20") (pin "2") (pinfunction "2_2") (pintype "passive"))
      (node (ref "U3") (pin "4") (pinfunction "PB11/UART3_RX/I2C2_SDA_4") (pintype "bidirectional"))
    )
    (net (code "76") (name "/UART3_TX") (class "Default")
      (node (ref "R34") (pin "2") (pinfunction "2_2") (pintype "passive"))
      (node (ref "U3") (pin "3") (pinfunction "PB10/UART3_TX/I2C2_SCL_3") (pintype "bidirectional"))
    )
    (net (code "77") (name "/USB_N") (class "Default")
      (node (ref "P9") (pin "A7") (pinfunction "D-_A7") (pintype "bidirectional"))
      (node (ref "P9") (pin "B7") (pinfunction "D-_B7") (pintype "bidirectional"))
      (node (ref "U3") (pin "16") (pinfunction "PB6/USB2DM/UART1X_TX_16") (pintype "bidirectional"))
    )
    (net (code "78") (name "/USB_P") (class "Default")
      (node (ref "P9") (pin "A6") (pinfunction "D+_A6") (pintype "bidirectional"))
      (node (ref "P9") (pin "B6") (pinfunction "D+_B6") (pintype "bidirectional"))
      (node (ref "U3") (pin "17") (pinfunction "PB7/USB2DP/UART1X_RX_17") (pintype "bidirectional"))
    )
    (net (code "79") (name "/VBAT") (class "Default")
      (node (ref "C9") (pin "1") (pinfunction "1_1") (pintype "passive"))
      (node (ref "J3") (pin "33") (pinfunction "33_33") (pintype "passive"))
      (node (ref "U2") (pin "1") (pinfunction "VBAT_1") (pintype "power_in"))
    )
    (net (code "80") (name "/VDD") (class "Default")
      (node (ref "C4") (pin "2") (pinfunction "2_2") (pintype "passive"))
      (node (ref "C7") (pin "2") (pinfunction "2_2") (pintype "passive"))
      (node (ref "R12") (pin "2") (pinfunction "2_2") (pintype "passive"))
      (node (ref "R15") (pin "2") (pinfunction "2_2") (pintype "passive"))
      (node (ref "R16") (pin "1") (pinfunction "1_1") (pintype "passive"))
      (node (ref "R7") (pin "2") (pinfunction "2_2") (pintype "passive"))
      (node (ref "U2") (pin "19") (pinfunction "VDD_4_19") (pintype "power_in"))
    )
    (net (code "81") (name "/VDDA") (class "Default")
      (node (ref "C10") (pin "1") (pinfunction "1_1") (pintype "passive"))
      (node (ref "J4") (pin "5") (pinfunction "5_5") (pintype "passive"))
      (node (ref "J7") (pin "3") (pinfunction "3_3") (pintype "passive"))
      (node (ref "R12") (pin "1") (pinfunction "1_1") (pintype "passive"))
      (node (ref "U2") (pin "13") (pinfunction "VDDA_13") (pintype "power_in"))
    )
    (net (code "82") (name "/VIO") (class "Default")
      (node (ref "C1") (pin "2") (pinfunction "2_2") (pintype "passive"))
      (node (ref "C3") (pin "2") (pinfunction "2_2") (pintype "passive"))
      (node (ref "J4") (pin "20") (pinfunction "20_20") (pintype "passive"))
      (node (ref "R15") (pin "1") (pinfunction "1_1") (pintype "passive"))
      (node (ref "U2") (pin "32") (pinfunction "VIO_1_32") (pintype "power_in"))
      (node (ref "U2") (pin "64") (pinfunction "VIO_3_64") (pintype "power_in"))
    )
    (net (code "83") (name "3V3") (class "Default")
      (node (ref "C21") (pin "1") (pinfunction "1_1") (pintype "passive"))
      (node (ref "D2") (pin "1") (pinfunction "A_1") (pintype "passive"))
      (node (ref "D3") (pin "1") (pinfunction "A_1") (pintype "passive"))
      (node (ref "J2") (pin "7") (pinfunction "7_7") (pintype "passive"))
      (node (ref "J3") (pin "1") (pinfunction "1_1") (pintype "passive"))
      (node (ref "J3") (pin "12") (pinfunction "12_12") (pintype "passive"))
      (node (ref "J3") (pin "16") (pinfunction "16_16") (pintype "passive"))
      (node (ref "J3") (pin "2") (pinfunction "2_2") (pintype "passive"))
      (node (ref "J3") (pin "3") (pinfunction "3_3") (pintype "passive"))
      (node (ref "J3") (pin "4") (pinfunction "4_4") (pintype "passive"))
      (node (ref "J5") (pin "2") (pinfunction "2_2") (pintype "passive"))
      (node (ref "J5") (pin "4") (pinfunction "4_4") (pintype "passive"))
      (node (ref "R1") (pin "2") (pinfunction "2_2") (pintype "passive"))
      (node (ref "R14") (pin "2") (pinfunction "2_2") (pintype "passive"))
      (node (ref "R2") (pin "1") (pinfunction "1_1") (pintype "passive"))
      (node (ref "R24") (pin "2") (pinfunction "2_2") (pintype "passive"))
      (node (ref "R3") (pin "1") (pinfunction "1_1") (pintype "passive"))
      (node (ref "R7") (pin "1") (pinfunction "1_1") (pintype "passive"))
      (node (ref "S3") (pin "3") (pinfunction "3_3") (pintype "passive"))
      (node (ref "U3") (pin "14") (pinfunction "VDD33/VIO_14") (pintype "power_in"))
    )
    (net (code "84") (name "5V_in") (class "Default")
      (node (ref "F2") (pin "1") (pinfunction "1_1") (pintype "passive"))
      (node (ref "P7") (pin "A4") (pinfunction "VBUS_A4") (pintype "bidirectional"))
      (node (ref "P7") (pin "B4") (pinfunction "VBUS_B4") (pintype "bidirectional"))
      (node (ref "P9") (pin "A4") (pinfunction "VBUS_A4") (pintype "bidirectional"))
      (node (ref "P9") (pin "B4") (pinfunction "VBUS_B4") (pintype "bidirectional"))
    )
    (net (code "85") (name "GND") (class "Default")
      (node (ref "C1") (pin "1") (pinfunction "1_1") (pintype "passive"))
      (node (ref "C10") (pin "2") (pinfunction "2_2") (pintype "passive"))
      (node (ref "C11") (pin "1") (pinfunction "1_1") (pintype "passive"))
      (node (ref "C12") (pin "2") (pinfunction "2_2") (pintype "passive"))
      (node (ref "C13") (pin "2") (pinfunction "2_2") (pintype "passive"))
      (node (ref "C2") (pin "1") (pinfunction "1_1") (pintype "passive"))
      (node (ref "C21") (pin "2") (pinfunction "2_2") (pintype "passive"))
      (node (ref "C3") (pin "1") (pinfunction "1_1") (pintype "passive"))
      (node (ref "C31") (pin "1") (pinfunction "1_1") (pintype "passive"))
      (node (ref "C32") (pin "1") (pinfunction "1_1") (pintype "passive"))
      (node (ref "C4") (pin "1") (pinfunction "1_1") (pintype "passive"))
      (node (ref "C5") (pin "2") (pinfunction "2_2") (pintype "passive"))
      (node (ref "C6") (pin "2") (pinfunction "2_2") (pintype "passive"))
      (node (ref "C7") (pin "1") (pinfunction "1_1") (pintype "passive"))
      (node (ref "C8") (pin "1") (pinfunction "1_1") (pintype "passive"))
      (node (ref "C9") (pin "2") (pinfunction "2_2") (pintype "passive"))
      (node (ref "J2") (pin "5") (pinfunction "5_5") (pintype "passive"))
      (node (ref "J2") (pin "6") (pinfunction "6_6") (pintype "passive"))
      (node (ref "J3") (pin "19") (pinfunction "19_19") (pintype "passive"))
      (node (ref "J3") (pin "20") (pinfunction "20_20") (pintype "passive"))
      (node (ref "J3") (pin "21") (pinfunction "21_21") (pintype "passive"))
      (node (ref "J3") (pin "22") (pinfunction "22_22") (pintype "passive"))
      (node (ref "J3") (pin "7") (pinfunction "7_7") (pintype "passive"))
      (node (ref "J3") (pin "8") (pinfunction "8_8") (pintype "passive"))
      (node (ref "J4") (pin "32") (pinfunction "32_32") (pintype "passive"))
      (node (ref "J4") (pin "7") (pinfunction "7_7") (pintype "passive"))
      (node (ref "J5") (pin "6") (pinfunction "6_6") (pintype "passive"))
      (node (ref "J5") (pin "7") (pinfunction "7_7") (pintype "passive"))
      (node (ref "J7") (pin "4") (pinfunction "4_4") (pintype "passive"))
      (node (ref "P7") (pin "A1") (pinfunction "GND_A1") (pintype "bidirectional"))
      (node (ref "P7") (pin "B1") (pinfunction "GND_B1") (pintype "bidirectional"))
      (node (ref "P9") (pin "A1") (pinfunction "GND_A1") (pintype "bidirectional"))
      (node (ref "P9") (pin "B1") (pinfunction "GND_B1") (pintype "bidirectional"))
      (node (ref "PWR") (pin "2") (pinfunction "K_2") (pintype "passive"))
      (node (ref "R10") (pin "2") (pinfunction "2_2") (pintype "passive"))
      (node (ref "R11") (pin "2") (pinfunction "2_2") (pintype "passive"))
      (node (ref "R21") (pin "1") (pinfunction "1_1") (pintype "passive"))
      (node (ref "R22") (pin "1") (pinfunction "1_1") (pintype "passive"))
      (node (ref "R8") (pin "1") (pinfunction "1_1") (pintype "passive"))
      (node (ref "R9") (pin "1") (pinfunction "1_1") (pintype "passive"))
      (node (ref "S1") (pin "3") (pinfunction "B1_3") (pintype "passive"))
      (node (ref "S2") (pin "3") (pinfunction "B1_3") (pintype "passive"))
      (node (ref "S5") (pin "2") (pinfunction "2_2") (pintype "passive"))
      (node (ref "U1") (pin "1") (pinfunction "GND_1") (pintype "passive"))
      (node (ref "U2") (pin "12") (pinfunction "VSSA_12") (pintype "power_in"))
      (node (ref "U2") (pin "18") (pinfunction "VSS_4_18") (pintype "power_in"))
      (node (ref "U2") (pin "31") (pinfunction "VSS_1_31") (pintype "power_in"))
      (node (ref "U2") (pin "63") (pinfunction "VSS_3_63") (pintype "power_in"))
      (node (ref "U3") (pin "18") (pinfunction "VSS/GND_18") (pintype "power_in"))
    )
    (net (code "86") (name "Net-(D2-K)") (class "Default")
      (node (ref "D2") (pin "2") (pinfunction "K_2") (pintype "passive"))
      (node (ref "R13") (pin "2") (pinfunction "2_2") (pintype "passive"))
    )
    (net (code "87") (name "Net-(D3-K)") (class "Default")
      (node (ref "D3") (pin "2") (pinfunction "K_2") (pintype "passive"))
      (node (ref "R21") (pin "2") (pinfunction "2_2") (pintype "passive"))
    )
    (net (code "88") (name "Net-(J3-Pad6)") (class "Default")
      (node (ref "J3") (pin "6") (pinfunction "6_6") (pintype "passive"))
      (node (ref "R5") (pin "1") (pinfunction "1_1") (pintype "passive"))
    )
    (net (code "89") (name "Net-(J3-Pad10)") (class "Default")
      (node (ref "J3") (pin "10") (pinfunction "10_10") (pintype "passive"))
      (node (ref "J5") (pin "1") (pinfunction "1_1") (pintype "passive"))
    )
    (net (code "90") (name "Net-(LED1-A)") (class "Default")
      (node (ref "LED1") (pin "1") (pinfunction "A_1") (pintype "passive"))
      (node (ref "R2") (pin "2") (pinfunction "2_2") (pintype "passive"))
    )
    (net (code "91") (name "Net-(LED2-A)") (class "Default")
      (node (ref "LED2") (pin "1") (pinfunction "A_1") (pintype "passive"))
      (node (ref "R3") (pin "2") (pinfunction "2_2") (pintype "passive"))
    )
    (net (code "92") (name "Net-(P7-CC-PadA5)") (class "Default")
      (node (ref "P7") (pin "A5") (pinfunction "CC_A5") (pintype "bidirectional"))
      (node (ref "R8") (pin "2") (pinfunction "2_2") (pintype "passive"))
    )
    (net (code "93") (name "Net-(P7-CC-PadB5)") (class "Default")
      (node (ref "P7") (pin "B5") (pinfunction "CC_B5") (pintype "bidirectional"))
      (node (ref "R9") (pin "2") (pinfunction "2_2") (pintype "passive"))
    )
    (net (code "94") (name "Net-(P9-CC-PadA5)") (class "Default")
      (node (ref "P9") (pin "A5") (pinfunction "CC_A5") (pintype "bidirectional"))
      (node (ref "R10") (pin "1") (pinfunction "1_1") (pintype "passive"))
    )
    (net (code "95") (name "Net-(P9-CC-PadB5)") (class "Default")
      (node (ref "P9") (pin "B5") (pinfunction "CC_B5") (pintype "bidirectional"))
      (node (ref "R11") (pin "1") (pinfunction "1_1") (pintype "passive"))
    )
    (net (code "96") (name "Net-(PWR-A)") (class "Default")
      (node (ref "PWR") (pin "1") (pinfunction "A_1") (pintype "passive"))
      (node (ref "R1") (pin "1") (pinfunction "1_1") (pintype "passive"))
    )
    (net (code "97") (name "Net-(U1-VOUT)") (class "Default")
      (node (ref "C13") (pin "1") (pinfunction "1_1") (pintype "passive"))
      (node (ref "S3") (pin "1") (pinfunction "1_1") (pintype "passive"))
      (node (ref "U1") (pin "2") (pinfunction "VOUT_2") (pintype "passive"))
    )
    (net (code "98") (name "Net-(U2-VDD_2)") (class "Default")
      (node (ref "R16") (pin "2") (pinfunction "2_2") (pintype "passive"))
      (node (ref "U2") (pin "48") (pinfunction "VDD_2_48") (pintype "power_in"))
    )
    (net (code "99") (name "Net-(U2-VSS_2)") (class "Default")
      (node (ref "R22") (pin "2") (pinfunction "2_2") (pintype "passive"))
      (node (ref "U2") (pin "47") (pinfunction "VSS_2_47") (pintype "power_in"))
    )
    (net (code "100") (name "unconnected-(P7-RFU1-PadA8)") (class "Default")
      (node (ref "P7") (pin "A8") (pinfunction "RFU1_A8") (pintype "bidirectional+no_connect"))
    )
    (net (code "101") (name "unconnected-(P7-RFU1-PadB8)") (class "Default")
      (node (ref "P7") (pin "B8") (pinfunction "RFU1_B8") (pintype "bidirectional+no_connect"))
    )
    (net (code "102") (name "unconnected-(P9-RFU1-PadA8)") (class "Default")
      (node (ref "P9") (pin "A8") (pinfunction "RFU1_A8") (pintype "bidirectional+no_connect"))
    )
    (net (code "103") (name "unconnected-(P9-RFU1-PadB8)") (class "Default")
      (node (ref "P9") (pin "B8") (pinfunction "RFU1_B8") (pintype "bidirectional+no_connect"))
    )
    (net (code "104") (name "unconnected-(S1-A1-Pad4)") (class "Default")
      (node (ref "S1") (pin "4") (pinfunction "A1_4") (pintype "passive"))
    )
    (net (code "105") (name "unconnected-(S1-B0-Pad2)") (class "Default")
      (node (ref "S1") (pin "2") (pinfunction "B0_2") (pintype "passive"))
    )
    (net (code "106") (name "unconnected-(S2-A1-Pad4)") (class "Default")
      (node (ref "S2") (pin "4") (pinfunction "A1_4") (pintype "passive"))
    )
    (net (code "107") (name "unconnected-(S2-B0-Pad2)") (class "Default")
      (node (ref "S2") (pin "2") (pinfunction "B0_2") (pintype "passive"))
    )
    (net (code "108") (name "unconnected-(S3-Pad2)") (class "Default")
      (node (ref "S3") (pin "2") (pinfunction "2_2") (pintype "passive"))
    )
    (net (code "109") (name "unconnected-(U3-PA5{slash}UART1_CTS{slash}PA1_(no5V)-Pad2)") (class "Default")
      (node (ref "U3") (pin "2") (pinfunction "PA5/UART1_CTS/PA1_(no5V)_2") (pintype "bidirectional+no_connect"))
    )
    (net (code "110") (name "unconnected-(U3-PB12{slash}SPI2_NSS{slash}CAN2_RX-Pad5)") (class "Default")
      (node (ref "U3") (pin "5") (pinfunction "PB12/SPI2_NSS/CAN2_RX_5") (pintype "bidirectional+no_connect"))
    )
    (net (code "111") (name "unconnected-(U3-PB14{slash}SPI2_MISO{slash}UART3_RTS-Pad7)") (class "Default")
      (node (ref "U3") (pin "7") (pinfunction "PB14/SPI2_MISO/UART3_RTS_7") (pintype "bidirectional+no_connect"))
    )
    (net (code "112") (name "unconnected-(U3-PB15{slash}SPI2_MOSI{slash}UART1_TX-Pad8)") (class "Default")
      (node (ref "U3") (pin "8") (pinfunction "PB15/SPI2_MOSI/UART1_TX_8") (pintype "bidirectional+no_connect"))
    )
  )
)
